# 130818_I_T_V_AriloRX_FINAL.net
KiCad netlist of a schematic drawn in EAGLE
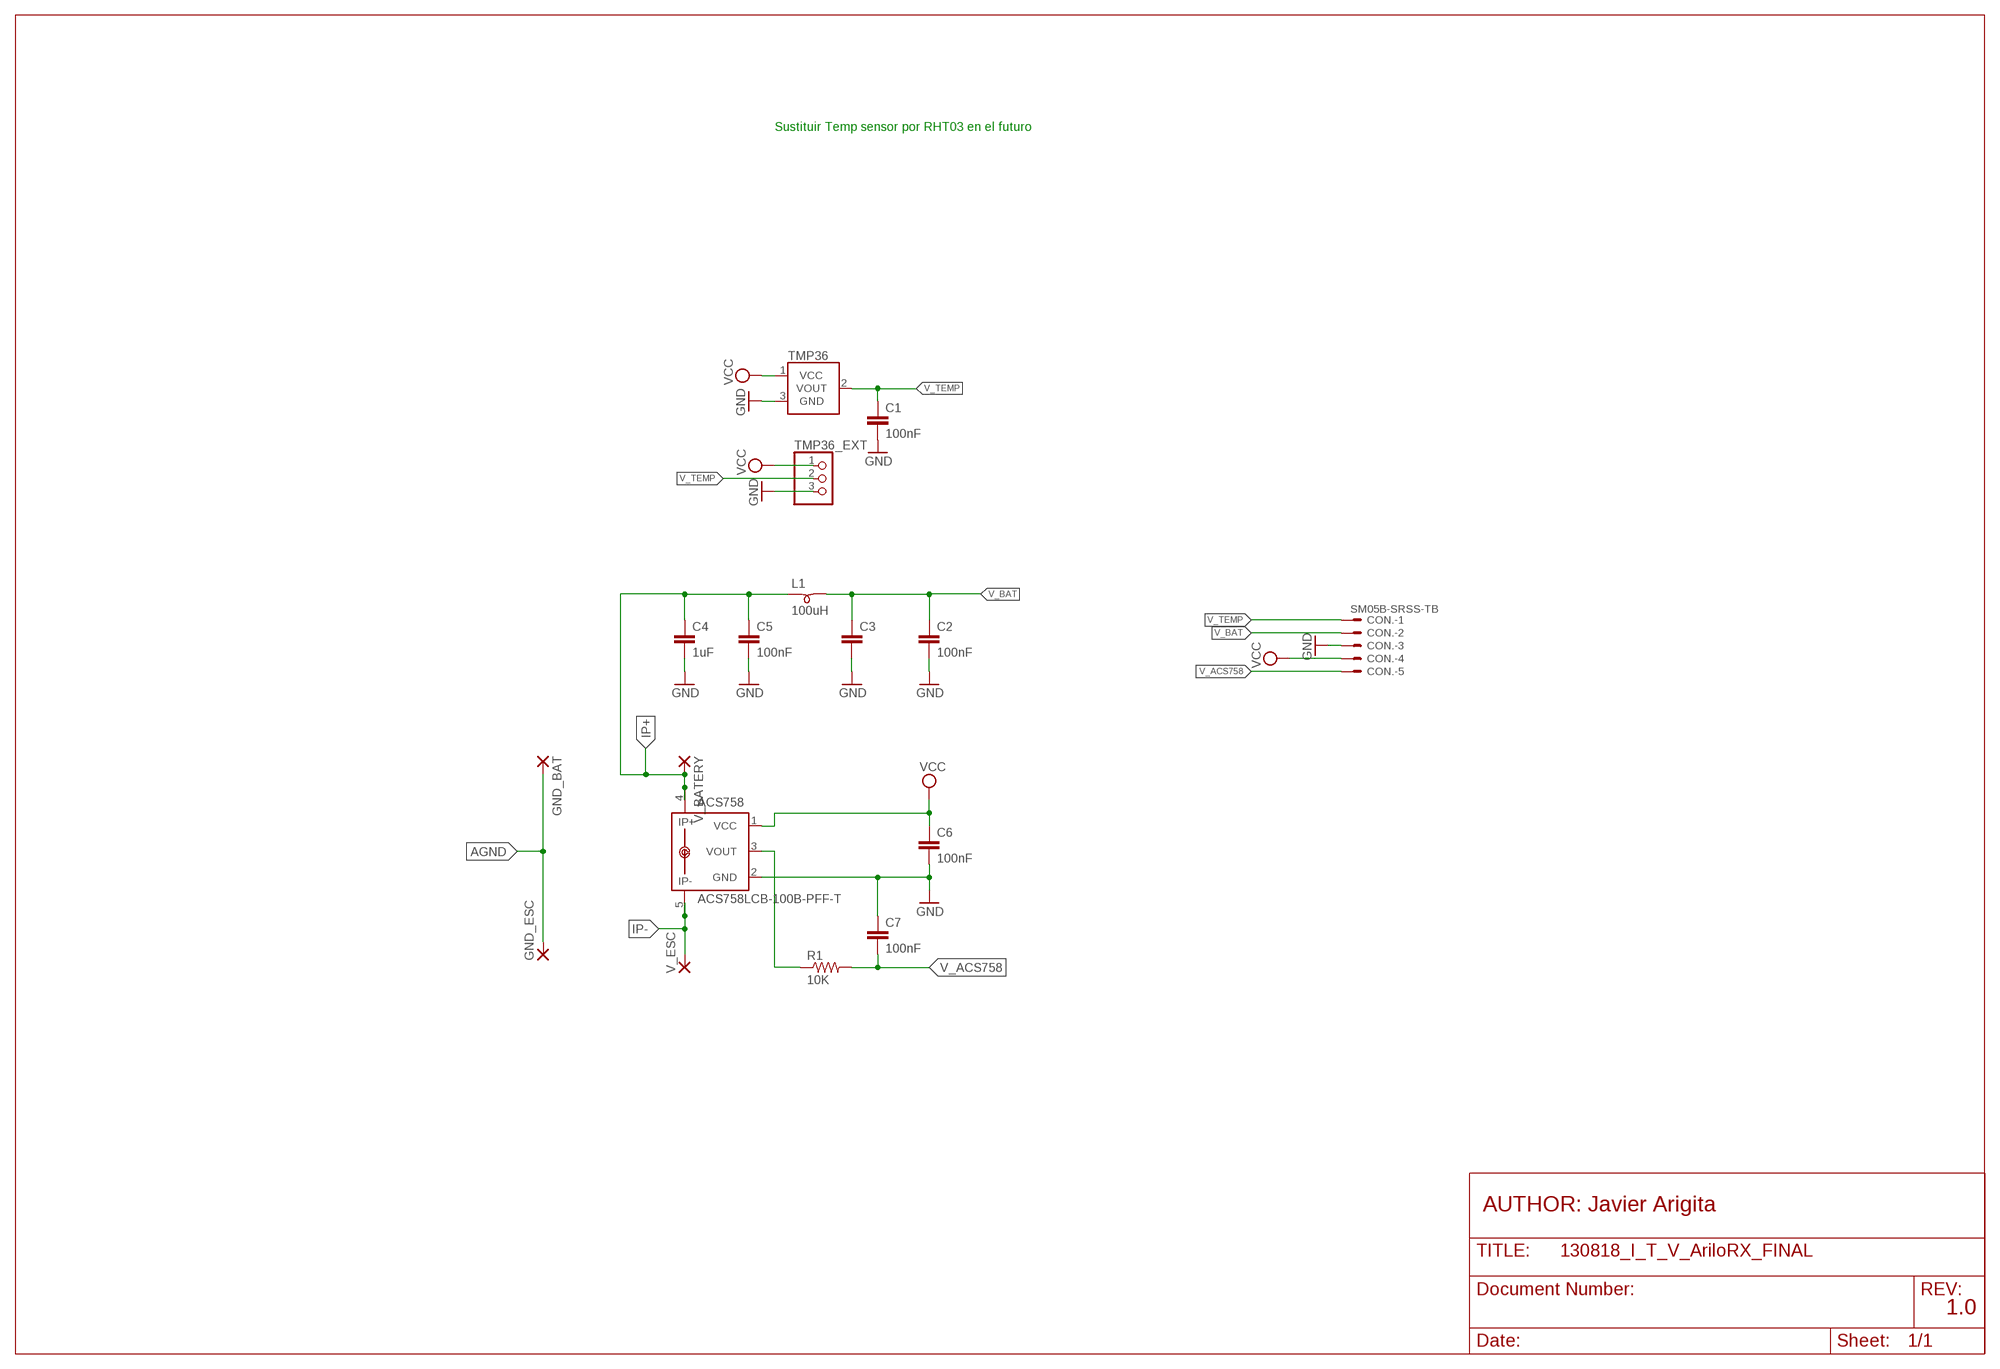
[diagram p0: schematic, sheet 1]

(export (version "E")
  (design (tool "Eeschema 10.0.6"))
  (components
    (comp (ref "ACS758")
      (value "ACS758LCB-100B-PFF-T")
      (footprint "eagle-import:CB-PFF")
      (libsource (lib "eagle-import") (part "ACS758LCB-100B-PFF-T"))
    )
    (comp (ref "C1")
      (value "100nF")
      (footprint "eagle-import:C0805")
      (libsource (lib "eagle-import") (part "C-EUC0805"))
    )
    (comp (ref "C2")
      (value "100nF")
      (footprint "eagle-import:C0805")
      (libsource (lib "eagle-import") (part "C-EUC0805"))
    )
    (comp (ref "C3")
      (value "C-EUC3216")
      (footprint "eagle-import:C3216")
      (libsource (lib "eagle-import") (part "C-EUC3216"))
    )
    (comp (ref "C4")
      (value "1uF")
      (footprint "eagle-import:C3216")
      (libsource (lib "eagle-import") (part "C-EUC3216"))
    )
    (comp (ref "C5")
      (value "100nF")
      (footprint "eagle-import:C0805")
      (libsource (lib "eagle-import") (part "C-EUC0805"))
    )
    (comp (ref "C6")
      (value "100nF")
      (footprint "eagle-import:C0805")
      (libsource (lib "eagle-import") (part "C-EUC0805"))
    )
    (comp (ref "C7")
      (value "100nF")
      (footprint "eagle-import:C0805")
      (libsource (lib "eagle-import") (part "C-EUC0805"))
    )
    (comp (ref "CON.")
      (value "SM05B-SRSS-TB")
      (footprint "eagle-import:SM05B-SRSS-TB")
      (libsource (lib "eagle-import") (part "?M05B-SRSS-TBS"))
    )
    (comp (ref "GND_BAT")
      (value "SMD5")
      (footprint "eagle-import:SMD2,54-5,08")
      (libsource (lib "eagle-import") (part "SMD5"))
    )
    (comp (ref "GND_ESC")
      (value "SMD5")
      (footprint "eagle-import:SMD2,54-5,08")
      (libsource (lib "eagle-import") (part "SMD5"))
    )
    (comp (ref "L1")
      (value "100uH")
      (footprint "eagle-import:SM-B5")
      (libsource (lib "eagle-import") (part "SM-B5"))
    )
    (comp (ref "R1")
      (value "10K")
      (footprint "eagle-import:R0805")
      (libsource (lib "eagle-import") (part "RESISTOR0805"))
    )
    (comp (ref "TMP36")
      (value "TMP36GT9")
      (footprint "eagle-import:TO-92")
      (libsource (lib "eagle-import") (part "TMP36GT9"))
    )
    (comp (ref "TMP36_EXT")
      (value "PINHD-1X3")
      (footprint "eagle-import:1X03")
      (libsource (lib "eagle-import") (part "PINHD-1X3"))
    )
    (comp (ref "V_BATERY")
      (value "SMD5")
      (footprint "eagle-import:SMD2,54-5,08")
      (libsource (lib "eagle-import") (part "SMD5"))
    )
    (comp (ref "V_ESC")
      (value "SMD5")
      (footprint "eagle-import:SMD2,54-5,08")
      (libsource (lib "eagle-import") (part "SMD5"))
    )
  )
  (nets
    (net (code "1") (name "AGND") (class "Default")
      (node (ref "GND_BAT") (pin "1") (pinfunction "P_1") (pintype "passive"))
      (node (ref "GND_ESC") (pin "1") (pinfunction "P_1") (pintype "passive"))
    )
    (net (code "2") (name "GND") (class "Default")
      (node (ref "ACS758") (pin "2") (pinfunction "GND_2") (pintype "power_in"))
      (node (ref "C1") (pin "2") (pinfunction "2_2") (pintype "passive"))
      (node (ref "C2") (pin "2") (pinfunction "2_2") (pintype "passive"))
      (node (ref "C3") (pin "2") (pinfunction "2_2") (pintype "passive"))
      (node (ref "C4") (pin "2") (pinfunction "2_2") (pintype "passive"))
      (node (ref "C5") (pin "2") (pinfunction "2_2") (pintype "passive"))
      (node (ref "C6") (pin "2") (pinfunction "2_2") (pintype "passive"))
      (node (ref "C7") (pin "1") (pinfunction "1_1") (pintype "passive"))
      (node (ref "CON.") (pin "3") (pinfunction "S_3") (pintype "passive"))
      (node (ref "TMP36") (pin "3") (pinfunction "GND_3") (pintype "bidirectional"))
      (node (ref "TMP36_EXT") (pin "3") (pinfunction "3_3") (pintype "passive"))
    )
    (net (code "3") (name "IP+") (class "Default")
      (node (ref "ACS758") (pin "4") (pinfunction "IP+_4") (pintype "passive"))
      (node (ref "ACS758") (pin "IP+1") (pinfunction "IP+1_IP+1") (pintype "input"))
      (node (ref "C4") (pin "1") (pinfunction "1_1") (pintype "passive"))
      (node (ref "C5") (pin "1") (pinfunction "1_1") (pintype "passive"))
      (node (ref "L1") (pin "1") (pinfunction "1_1") (pintype "passive"))
      (node (ref "V_BATERY") (pin "1") (pinfunction "P_1") (pintype "passive"))
    )
    (net (code "4") (name "IP-") (class "Default")
      (node (ref "ACS758") (pin "5") (pinfunction "IP-_5") (pintype "passive"))
      (node (ref "ACS758") (pin "IP-1") (pinfunction "IP-1_IP-1") (pintype "input"))
      (node (ref "V_ESC") (pin "1") (pinfunction "P_1") (pintype "passive"))
    )
    (net (code "5") (name "Net-(ACS758-VOUT)") (class "Default")
      (node (ref "ACS758") (pin "3") (pinfunction "VOUT_3") (pintype "output"))
      (node (ref "R1") (pin "1") (pinfunction "1_1") (pintype "passive"))
    )
    (net (code "6") (name "VCC") (class "Default")
      (node (ref "ACS758") (pin "1") (pinfunction "VCC_1") (pintype "power_in"))
      (node (ref "C6") (pin "1") (pinfunction "1_1") (pintype "passive"))
      (node (ref "CON.") (pin "4") (pinfunction "S_4") (pintype "passive"))
      (node (ref "TMP36") (pin "1") (pinfunction "VCC_1") (pintype "bidirectional"))
      (node (ref "TMP36_EXT") (pin "1") (pinfunction "1_1") (pintype "passive"))
    )
    (net (code "7") (name "V_ACS758") (class "Default")
      (node (ref "C7") (pin "2") (pinfunction "2_2") (pintype "passive"))
      (node (ref "CON.") (pin "5") (pinfunction "S_5") (pintype "passive"))
      (node (ref "R1") (pin "2") (pinfunction "2_2") (pintype "passive"))
    )
    (net (code "8") (name "V_BAT") (class "Default")
      (node (ref "C2") (pin "1") (pinfunction "1_1") (pintype "passive"))
      (node (ref "C3") (pin "1") (pinfunction "1_1") (pintype "passive"))
      (node (ref "CON.") (pin "2") (pinfunction "S_2") (pintype "passive"))
      (node (ref "L1") (pin "2") (pinfunction "2_2") (pintype "passive"))
    )
    (net (code "9") (name "V_TEMP") (class "Default")
      (node (ref "C1") (pin "1") (pinfunction "1_1") (pintype "passive"))
      (node (ref "CON.") (pin "1") (pinfunction "S_1") (pintype "passive"))
      (node (ref "TMP36") (pin "2") (pinfunction "VOUT_2") (pintype "bidirectional"))
      (node (ref "TMP36_EXT") (pin "2") (pinfunction "2_2") (pintype "passive"))
    )
  )
)
